# mymote-quake.net
KiCad netlist of a schematic drawn in EAGLE
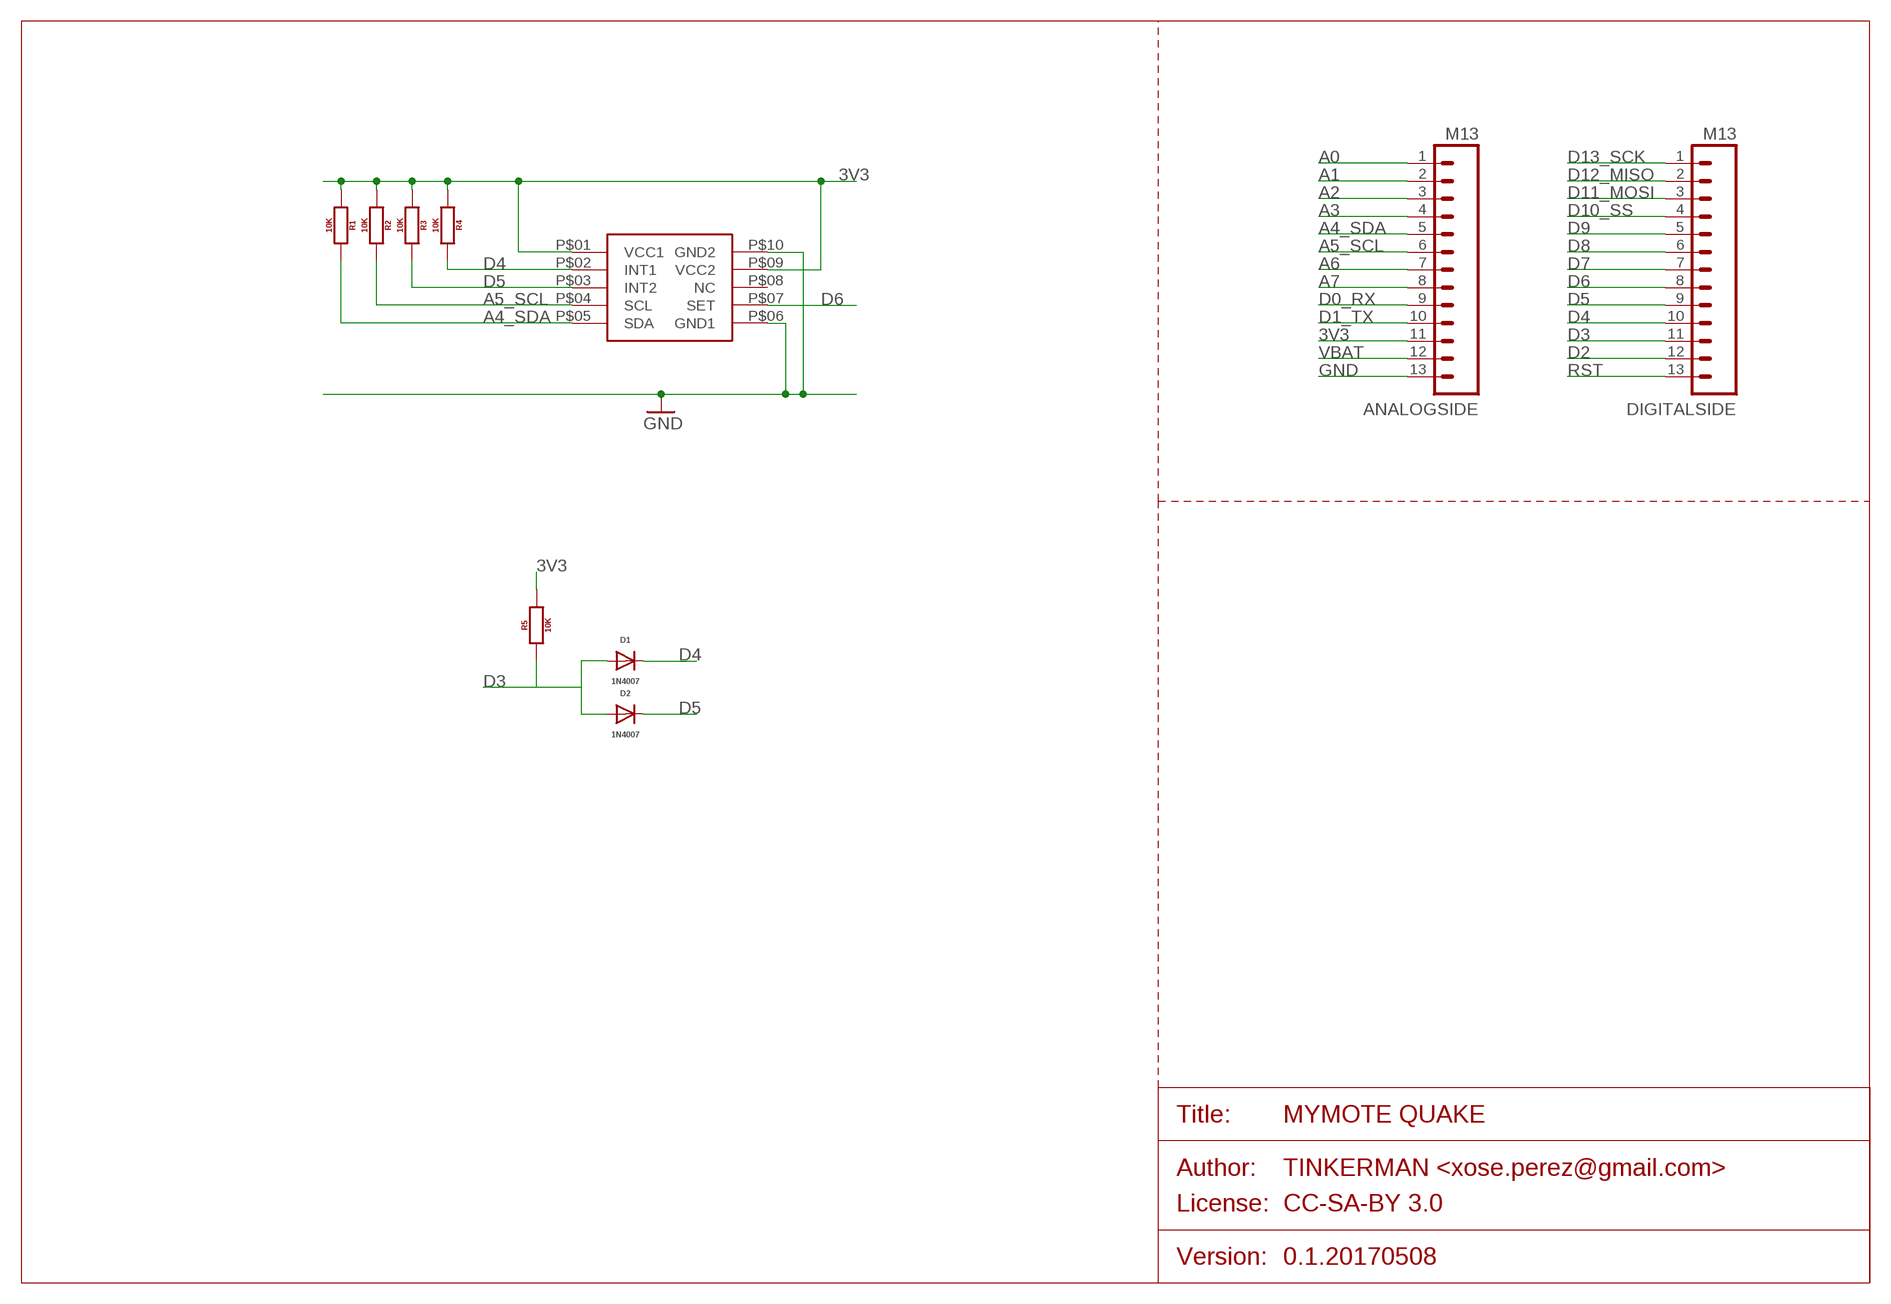
[diagram p0: schematic, sheet 1]

(export (version "E")
  (design (tool "Eeschema 10.0.6"))
  (components
    (comp (ref "ANALOGSIDE")
      (value "M13")
      (footprint "eagle-import:1X13_NO_SILK")
      (libsource (lib "eagle-import") (part "M13"))
    )
    (comp (ref "D1")
      (value "1N4007")
      (footprint "eagle-import:0805_DIODE")
      (libsource (lib "eagle-import") (part "DIODE-SMD"))
    )
    (comp (ref "D2")
      (value "1N4007")
      (footprint "eagle-import:0805_DIODE")
      (libsource (lib "eagle-import") (part "DIODE-SMD"))
    )
    (comp (ref "DIGITALSIDE")
      (value "M13")
      (footprint "eagle-import:1X13_NO_SILK")
      (libsource (lib "eagle-import") (part "M13"))
    )
    (comp (ref "R1")
      (value "10K")
      (footprint "eagle-import:0805")
      (libsource (lib "eagle-import") (part "RESISTOR0805"))
    )
    (comp (ref "R2")
      (value "10K")
      (footprint "eagle-import:0805")
      (libsource (lib "eagle-import") (part "RESISTOR0805"))
    )
    (comp (ref "R3")
      (value "10K")
      (footprint "eagle-import:0805")
      (libsource (lib "eagle-import") (part "RESISTOR0805"))
    )
    (comp (ref "R4")
      (value "10K")
      (footprint "eagle-import:0805")
      (libsource (lib "eagle-import") (part "RESISTOR0805"))
    )
    (comp (ref "R5")
      (value "10K")
      (footprint "eagle-import:0805")
      (libsource (lib "eagle-import") (part "RESISTOR0805"))
    )
    (comp (ref "U$1")
      (value "D7S-A0001")
      (footprint "eagle-import:D7S-A0001")
      (libsource (lib "eagle-import") (part "D7S-A0001"))
    )
  )
  (nets
    (net (code "1") (name "/3V3") (class "Default")
      (node (ref "ANALOGSIDE") (pin "11") (pinfunction "11_11") (pintype "passive"))
      (node (ref "R1") (pin "1") (pinfunction "1_1") (pintype "passive"))
      (node (ref "R2") (pin "1") (pinfunction "1_1") (pintype "passive"))
      (node (ref "R3") (pin "1") (pinfunction "1_1") (pintype "passive"))
      (node (ref "R4") (pin "1") (pinfunction "1_1") (pintype "passive"))
      (node (ref "R5") (pin "2") (pinfunction "2_2") (pintype "passive"))
      (node (ref "U$1") (pin "P$01") (pinfunction "VCC1_P$01") (pintype "power_in"))
      (node (ref "U$1") (pin "P$09") (pinfunction "VCC2_P$09") (pintype "power_in"))
    )
    (net (code "2") (name "/A0") (class "Default")
      (node (ref "ANALOGSIDE") (pin "1") (pinfunction "1_1") (pintype "passive"))
    )
    (net (code "3") (name "/A1") (class "Default")
      (node (ref "ANALOGSIDE") (pin "2") (pinfunction "2_2") (pintype "passive"))
    )
    (net (code "4") (name "/A2") (class "Default")
      (node (ref "ANALOGSIDE") (pin "3") (pinfunction "3_3") (pintype "passive"))
    )
    (net (code "5") (name "/A3") (class "Default")
      (node (ref "ANALOGSIDE") (pin "4") (pinfunction "4_4") (pintype "passive"))
    )
    (net (code "6") (name "/A4_SDA") (class "Default")
      (node (ref "ANALOGSIDE") (pin "5") (pinfunction "5_5") (pintype "passive"))
      (node (ref "R1") (pin "2") (pinfunction "2_2") (pintype "passive"))
      (node (ref "U$1") (pin "P$05") (pinfunction "SDA_P$05") (pintype "bidirectional"))
    )
    (net (code "7") (name "/A5_SCL") (class "Default")
      (node (ref "ANALOGSIDE") (pin "6") (pinfunction "6_6") (pintype "passive"))
      (node (ref "R2") (pin "2") (pinfunction "2_2") (pintype "passive"))
      (node (ref "U$1") (pin "P$04") (pinfunction "SCL_P$04") (pintype "input"))
    )
    (net (code "8") (name "/A6") (class "Default")
      (node (ref "ANALOGSIDE") (pin "7") (pinfunction "7_7") (pintype "passive"))
    )
    (net (code "9") (name "/A7") (class "Default")
      (node (ref "ANALOGSIDE") (pin "8") (pinfunction "8_8") (pintype "passive"))
    )
    (net (code "10") (name "/D0_RX") (class "Default")
      (node (ref "ANALOGSIDE") (pin "9") (pinfunction "9_9") (pintype "passive"))
    )
    (net (code "11") (name "/D1_TX") (class "Default")
      (node (ref "ANALOGSIDE") (pin "10") (pinfunction "10_10") (pintype "passive"))
    )
    (net (code "12") (name "/D2") (class "Default")
      (node (ref "DIGITALSIDE") (pin "12") (pinfunction "12_12") (pintype "passive"))
    )
    (net (code "13") (name "/D3") (class "Default")
      (node (ref "D1") (pin "A") (pinfunction "A_A") (pintype "passive"))
      (node (ref "D2") (pin "A") (pinfunction "A_A") (pintype "passive"))
      (node (ref "DIGITALSIDE") (pin "11") (pinfunction "11_11") (pintype "passive"))
      (node (ref "R5") (pin "1") (pinfunction "1_1") (pintype "passive"))
    )
    (net (code "14") (name "/D4") (class "Default")
      (node (ref "D1") (pin "C") (pinfunction "C_C") (pintype "passive"))
      (node (ref "DIGITALSIDE") (pin "10") (pinfunction "10_10") (pintype "passive"))
      (node (ref "R4") (pin "2") (pinfunction "2_2") (pintype "passive"))
      (node (ref "U$1") (pin "P$02") (pinfunction "INT1_P$02") (pintype "output"))
    )
    (net (code "15") (name "/D5") (class "Default")
      (node (ref "D2") (pin "C") (pinfunction "C_C") (pintype "passive"))
      (node (ref "DIGITALSIDE") (pin "9") (pinfunction "9_9") (pintype "passive"))
      (node (ref "R3") (pin "2") (pinfunction "2_2") (pintype "passive"))
      (node (ref "U$1") (pin "P$03") (pinfunction "INT2_P$03") (pintype "output"))
    )
    (net (code "16") (name "/D6") (class "Default")
      (node (ref "DIGITALSIDE") (pin "8") (pinfunction "8_8") (pintype "passive"))
      (node (ref "U$1") (pin "P$07") (pinfunction "SET_P$07") (pintype "input"))
    )
    (net (code "17") (name "/D7") (class "Default")
      (node (ref "DIGITALSIDE") (pin "7") (pinfunction "7_7") (pintype "passive"))
    )
    (net (code "18") (name "/D8") (class "Default")
      (node (ref "DIGITALSIDE") (pin "6") (pinfunction "6_6") (pintype "passive"))
    )
    (net (code "19") (name "/D9") (class "Default")
      (node (ref "DIGITALSIDE") (pin "5") (pinfunction "5_5") (pintype "passive"))
    )
    (net (code "20") (name "/D10_SS") (class "Default")
      (node (ref "DIGITALSIDE") (pin "4") (pinfunction "4_4") (pintype "passive"))
    )
    (net (code "21") (name "/D11_MOSI") (class "Default")
      (node (ref "DIGITALSIDE") (pin "3") (pinfunction "3_3") (pintype "passive"))
    )
    (net (code "22") (name "/D12_MISO") (class "Default")
      (node (ref "DIGITALSIDE") (pin "2") (pinfunction "2_2") (pintype "passive"))
    )
    (net (code "23") (name "/D13_SCK") (class "Default")
      (node (ref "DIGITALSIDE") (pin "1") (pinfunction "1_1") (pintype "passive"))
    )
    (net (code "24") (name "/RST") (class "Default")
      (node (ref "DIGITALSIDE") (pin "13") (pinfunction "13_13") (pintype "passive"))
    )
    (net (code "25") (name "/VBAT") (class "Default")
      (node (ref "ANALOGSIDE") (pin "12") (pinfunction "12_12") (pintype "passive"))
    )
    (net (code "26") (name "GND") (class "Default")
      (node (ref "ANALOGSIDE") (pin "13") (pinfunction "13_13") (pintype "passive"))
      (node (ref "U$1") (pin "P$06") (pinfunction "GND1_P$06") (pintype "power_in"))
      (node (ref "U$1") (pin "P$10") (pinfunction "GND2_P$10") (pintype "power_in"))
    )
    (net (code "27") (name "unconnected-(U$1-NC-PadP$08)") (class "Default")
      (node (ref "U$1") (pin "P$08") (pinfunction "NC_P$08") (pintype "no_connect"))
    )
  )
)
